# AS5600_Module.net
KiCad netlist of a schematic drawn in EAGLE
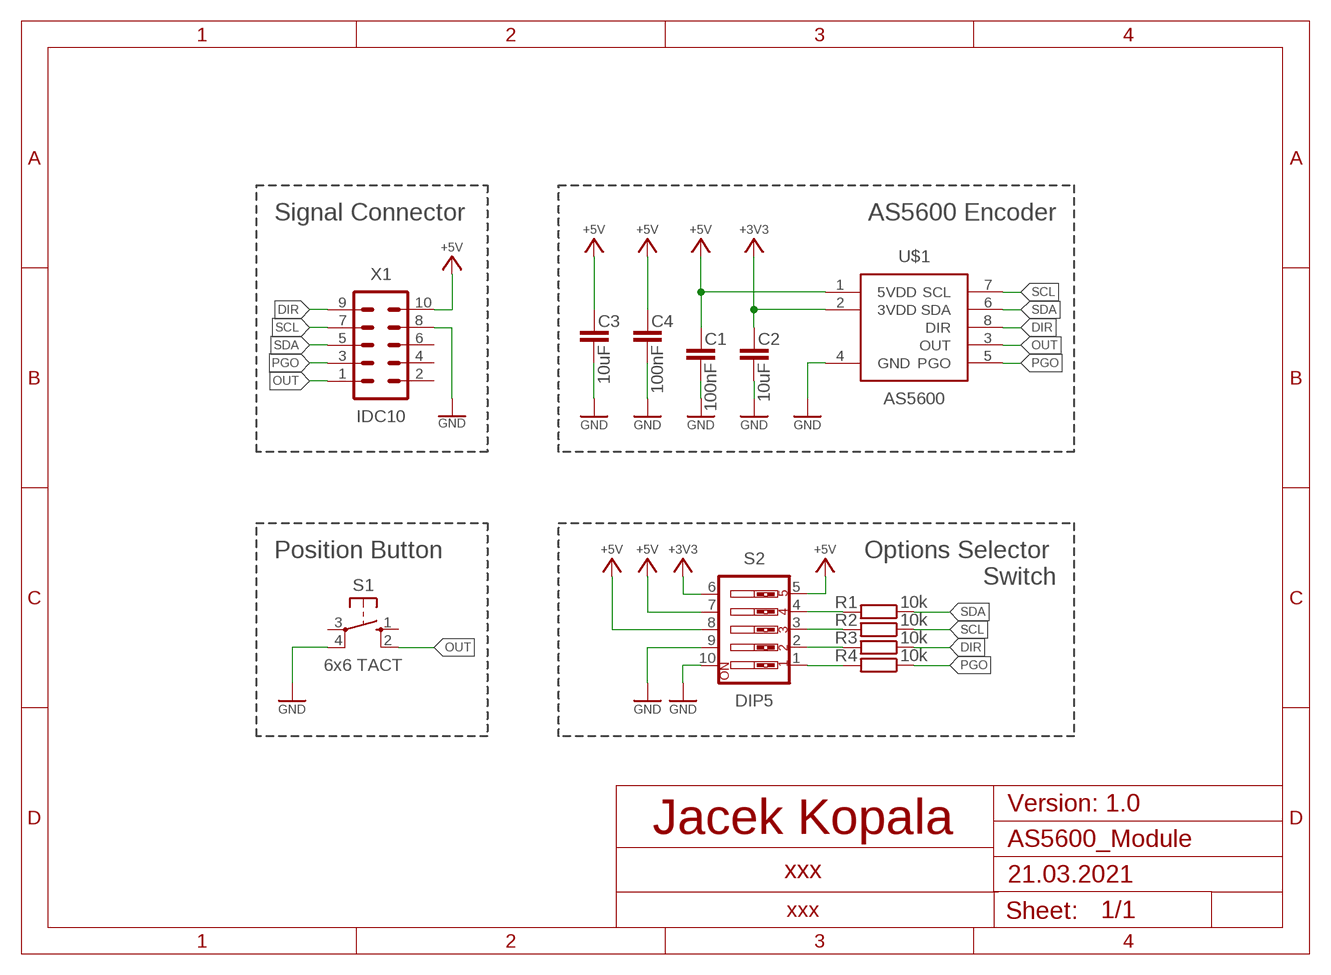
[diagram p0: schematic, sheet 1]

(export (version "E")
  (design (tool "Eeschema 10.0.6"))
  (components
    (comp (ref "C1")
      (value "100nF")
      (footprint "eagle-import:C0805K")
      (libsource (lib "eagle-import") (part "C-EUC0805K"))
    )
    (comp (ref "C2")
      (value "10uF")
      (footprint "eagle-import:C0805K")
      (libsource (lib "eagle-import") (part "C-EUC0805K"))
    )
    (comp (ref "C3")
      (value "10uF")
      (footprint "eagle-import:C0805K")
      (libsource (lib "eagle-import") (part "C-EUC0805K"))
    )
    (comp (ref "C4")
      (value "100nF")
      (footprint "eagle-import:C0805K")
      (libsource (lib "eagle-import") (part "C-EUC0805K"))
    )
    (comp (ref "R1")
      (value "10k")
      (footprint "eagle-import:R0805")
      (libsource (lib "eagle-import") (part "R-EU_R0805"))
    )
    (comp (ref "R2")
      (value "10k")
      (footprint "eagle-import:R0805")
      (libsource (lib "eagle-import") (part "R-EU_R0805"))
    )
    (comp (ref "R3")
      (value "10k")
      (footprint "eagle-import:R0805")
      (libsource (lib "eagle-import") (part "R-EU_R0805"))
    )
    (comp (ref "R4")
      (value "10k")
      (footprint "eagle-import:R0805")
      (libsource (lib "eagle-import") (part "R-EU_R0805"))
    )
    (comp (ref "S1")
      (value "6x6 TACT")
      (footprint "eagle-import:B3F-10XX")
      (fields (field (name "MPN") "B3F-1000"))
      (libsource (lib "eagle-import") (part "10-XX"))
    )
    (comp (ref "S2")
      (value "DIP5")
      (footprint "eagle-import:EDG-05")
      (libsource (lib "eagle-import") (part "SW_DIP-5"))
    )
    (comp (ref "U$1")
      (value "AS5600")
      (footprint "eagle-import:SO8")
      (libsource (lib "eagle-import") (part "AS5600"))
    )
    (comp (ref "X1")
      (value "IDC10")
      (footprint "eagle-import:ML10")
      (libsource (lib "eagle-import") (part "ML10"))
    )
  )
  (nets
    (net (code "1") (name "+3V3") (class "Default")
      (node (ref "C2") (pin "1") (pinfunction "1_1") (pintype "passive"))
      (node (ref "S2") (pin "6") (pinfunction "6_6") (pintype "passive"))
      (node (ref "U$1") (pin "2") (pinfunction "3VDD_2") (pintype "bidirectional"))
    )
    (net (code "2") (name "+5V") (class "Default")
      (node (ref "C1") (pin "1") (pinfunction "1_1") (pintype "passive"))
      (node (ref "C3") (pin "1") (pinfunction "1_1") (pintype "passive"))
      (node (ref "C4") (pin "1") (pinfunction "1_1") (pintype "passive"))
      (node (ref "S2") (pin "5") (pinfunction "5_5") (pintype "passive"))
      (node (ref "S2") (pin "7") (pinfunction "7_7") (pintype "passive"))
      (node (ref "S2") (pin "8") (pinfunction "8_8") (pintype "passive"))
      (node (ref "U$1") (pin "1") (pinfunction "5VDD_1") (pintype "bidirectional"))
      (node (ref "X1") (pin "10") (pinfunction "10_10") (pintype "passive"))
    )
    (net (code "3") (name "DIR") (class "Default")
      (node (ref "R3") (pin "1") (pinfunction "1_1") (pintype "passive"))
      (node (ref "U$1") (pin "8") (pinfunction "DIR_8") (pintype "bidirectional"))
      (node (ref "X1") (pin "9") (pinfunction "9_9") (pintype "passive"))
    )
    (net (code "4") (name "GND") (class "Default")
      (node (ref "C1") (pin "2") (pinfunction "2_2") (pintype "passive"))
      (node (ref "C2") (pin "2") (pinfunction "2_2") (pintype "passive"))
      (node (ref "C3") (pin "2") (pinfunction "2_2") (pintype "passive"))
      (node (ref "C4") (pin "2") (pinfunction "2_2") (pintype "passive"))
      (node (ref "S1") (pin "4") (pinfunction "P1_4") (pintype "passive"))
      (node (ref "S2") (pin "10") (pinfunction "10_10") (pintype "passive"))
      (node (ref "S2") (pin "9") (pinfunction "9_9") (pintype "passive"))
      (node (ref "U$1") (pin "4") (pinfunction "GND_4") (pintype "bidirectional"))
      (node (ref "X1") (pin "8") (pinfunction "8_8") (pintype "passive"))
    )
    (net (code "5") (name "Net-(R1-Pad2)") (class "Default")
      (node (ref "R1") (pin "2") (pinfunction "2_2") (pintype "passive"))
      (node (ref "S2") (pin "4") (pinfunction "4_4") (pintype "passive"))
    )
    (net (code "6") (name "Net-(R2-Pad2)") (class "Default")
      (node (ref "R2") (pin "2") (pinfunction "2_2") (pintype "passive"))
      (node (ref "S2") (pin "3") (pinfunction "3_3") (pintype "passive"))
    )
    (net (code "7") (name "Net-(R3-Pad2)") (class "Default")
      (node (ref "R3") (pin "2") (pinfunction "2_2") (pintype "passive"))
      (node (ref "S2") (pin "2") (pinfunction "2_2") (pintype "passive"))
    )
    (net (code "8") (name "Net-(R4-Pad2)") (class "Default")
      (node (ref "R4") (pin "2") (pinfunction "2_2") (pintype "passive"))
      (node (ref "S2") (pin "1") (pinfunction "1_1") (pintype "passive"))
    )
    (net (code "9") (name "OUT") (class "Default")
      (node (ref "S1") (pin "2") (pinfunction "S1_2") (pintype "passive"))
      (node (ref "U$1") (pin "3") (pinfunction "OUT_3") (pintype "bidirectional"))
      (node (ref "X1") (pin "1") (pinfunction "1_1") (pintype "passive"))
    )
    (net (code "10") (name "PGO") (class "Default")
      (node (ref "R4") (pin "1") (pinfunction "1_1") (pintype "passive"))
      (node (ref "U$1") (pin "5") (pinfunction "PGO_5") (pintype "bidirectional"))
      (node (ref "X1") (pin "3") (pinfunction "3_3") (pintype "passive"))
    )
    (net (code "11") (name "SCL") (class "Default")
      (node (ref "R2") (pin "1") (pinfunction "1_1") (pintype "passive"))
      (node (ref "U$1") (pin "7") (pinfunction "SCL_7") (pintype "bidirectional"))
      (node (ref "X1") (pin "7") (pinfunction "7_7") (pintype "passive"))
    )
    (net (code "12") (name "SDA") (class "Default")
      (node (ref "R1") (pin "1") (pinfunction "1_1") (pintype "passive"))
      (node (ref "U$1") (pin "6") (pinfunction "SDA_6") (pintype "bidirectional"))
      (node (ref "X1") (pin "5") (pinfunction "5_5") (pintype "passive"))
    )
    (net (code "13") (name "unconnected-(S1-P-Pad3)") (class "Default")
      (node (ref "S1") (pin "3") (pinfunction "P_3") (pintype "passive"))
    )
    (net (code "14") (name "unconnected-(S1-S-Pad1)") (class "Default")
      (node (ref "S1") (pin "1") (pinfunction "S_1") (pintype "passive"))
    )
    (net (code "15") (name "unconnected-(X1-Pad2)") (class "Default")
      (node (ref "X1") (pin "2") (pinfunction "2_2") (pintype "passive"))
    )
    (net (code "16") (name "unconnected-(X1-Pad4)") (class "Default")
      (node (ref "X1") (pin "4") (pinfunction "4_4") (pintype "passive"))
    )
    (net (code "17") (name "unconnected-(X1-Pad6)") (class "Default")
      (node (ref "X1") (pin "6") (pinfunction "6_6") (pintype "passive"))
    )
  )
)
